# Conn_C.net
KiCad netlist of a schematic drawn in Altium Designer
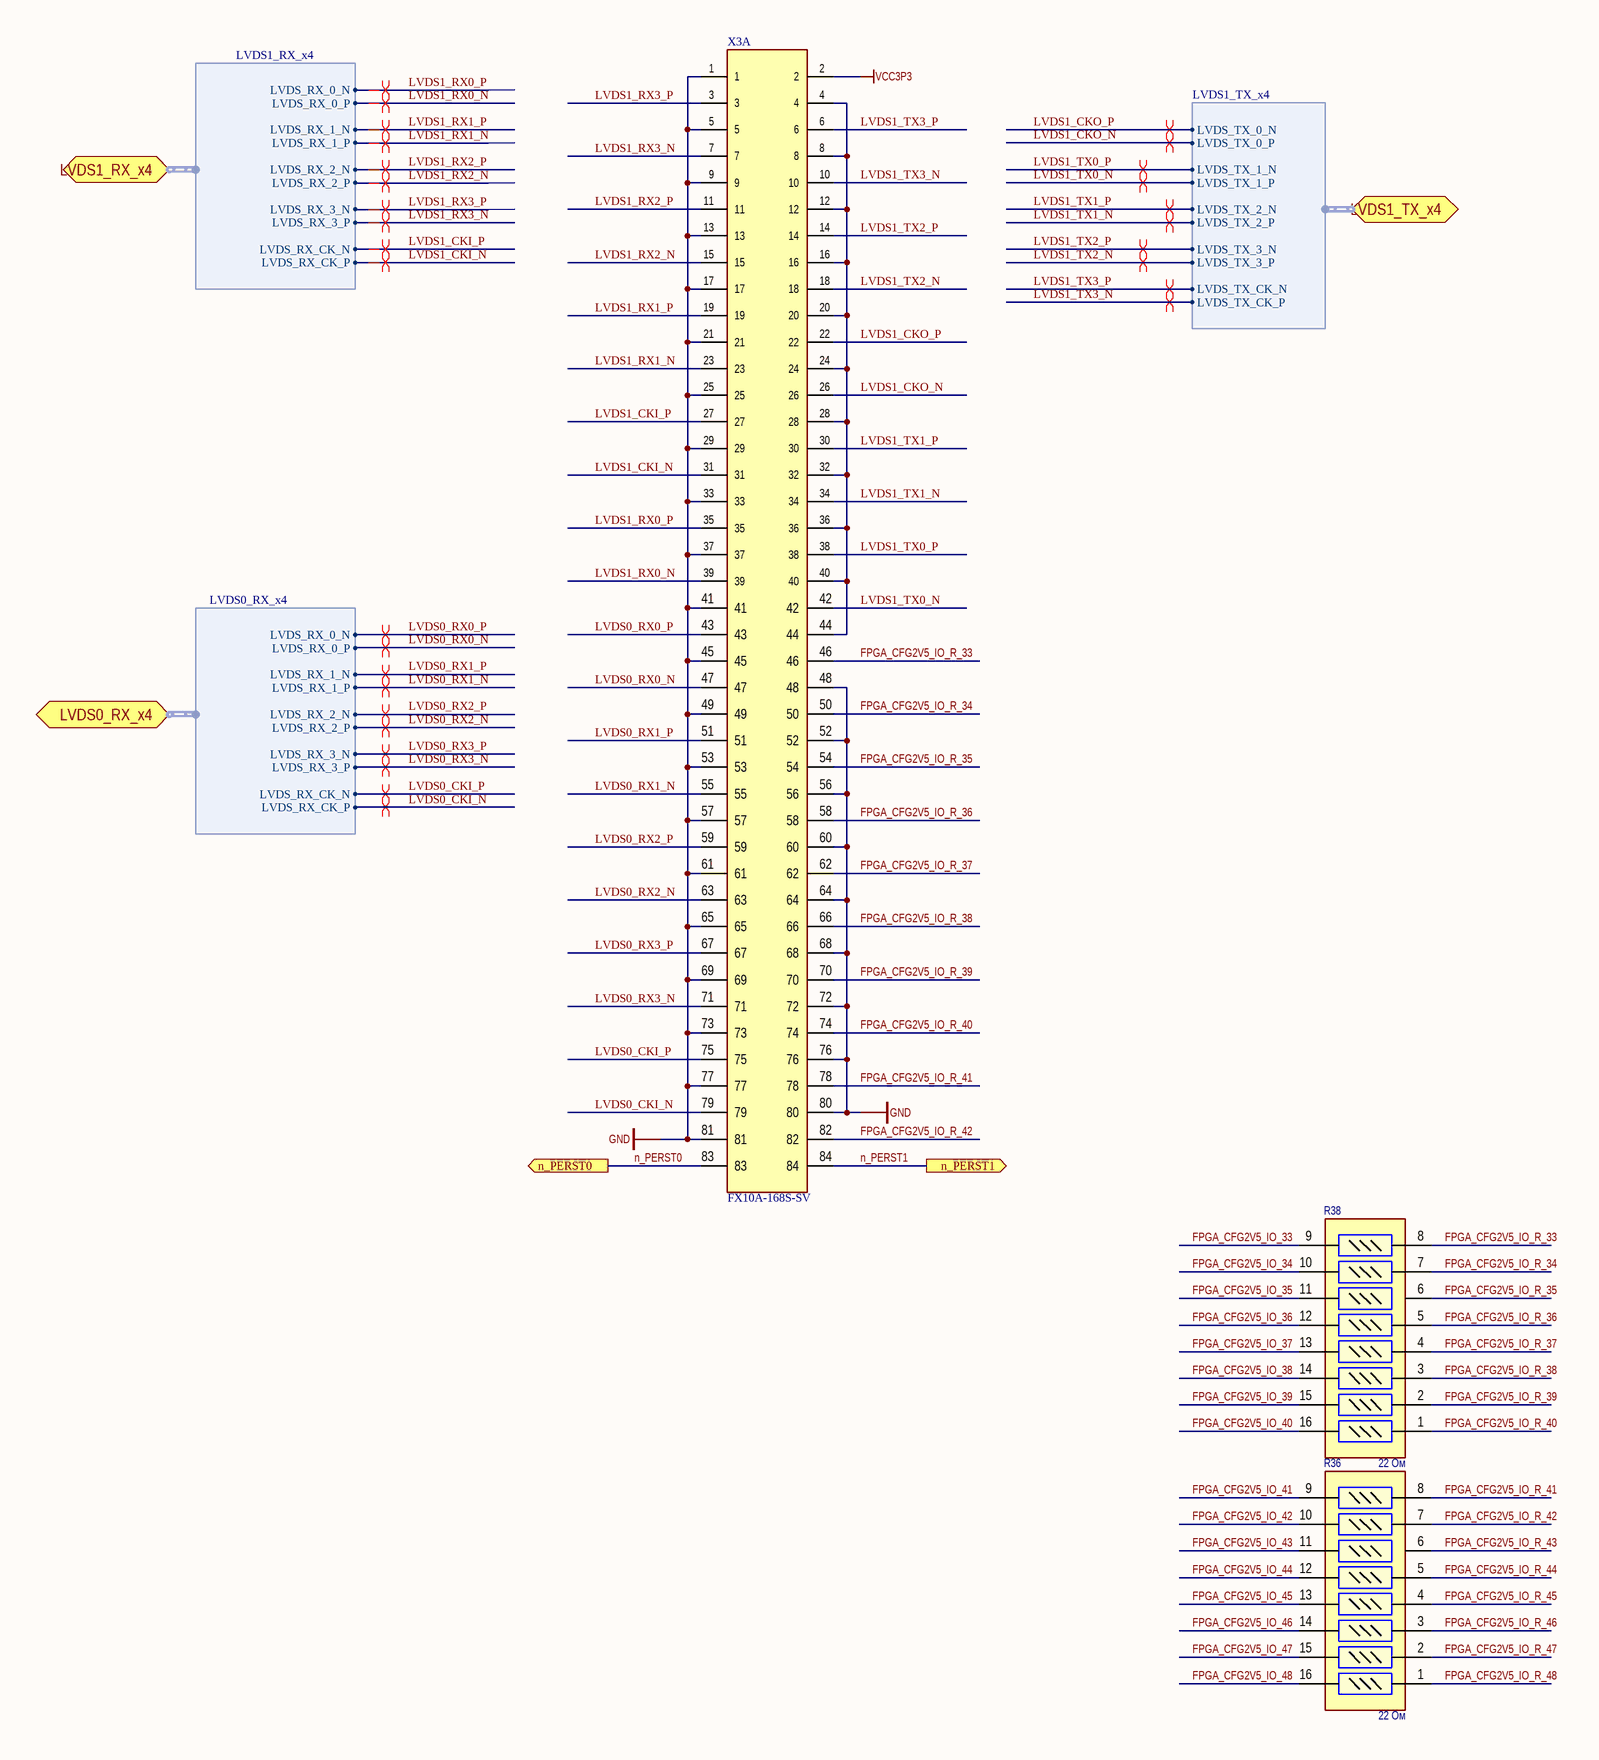
[diagram p0: Conn_C.SchDoc, left]
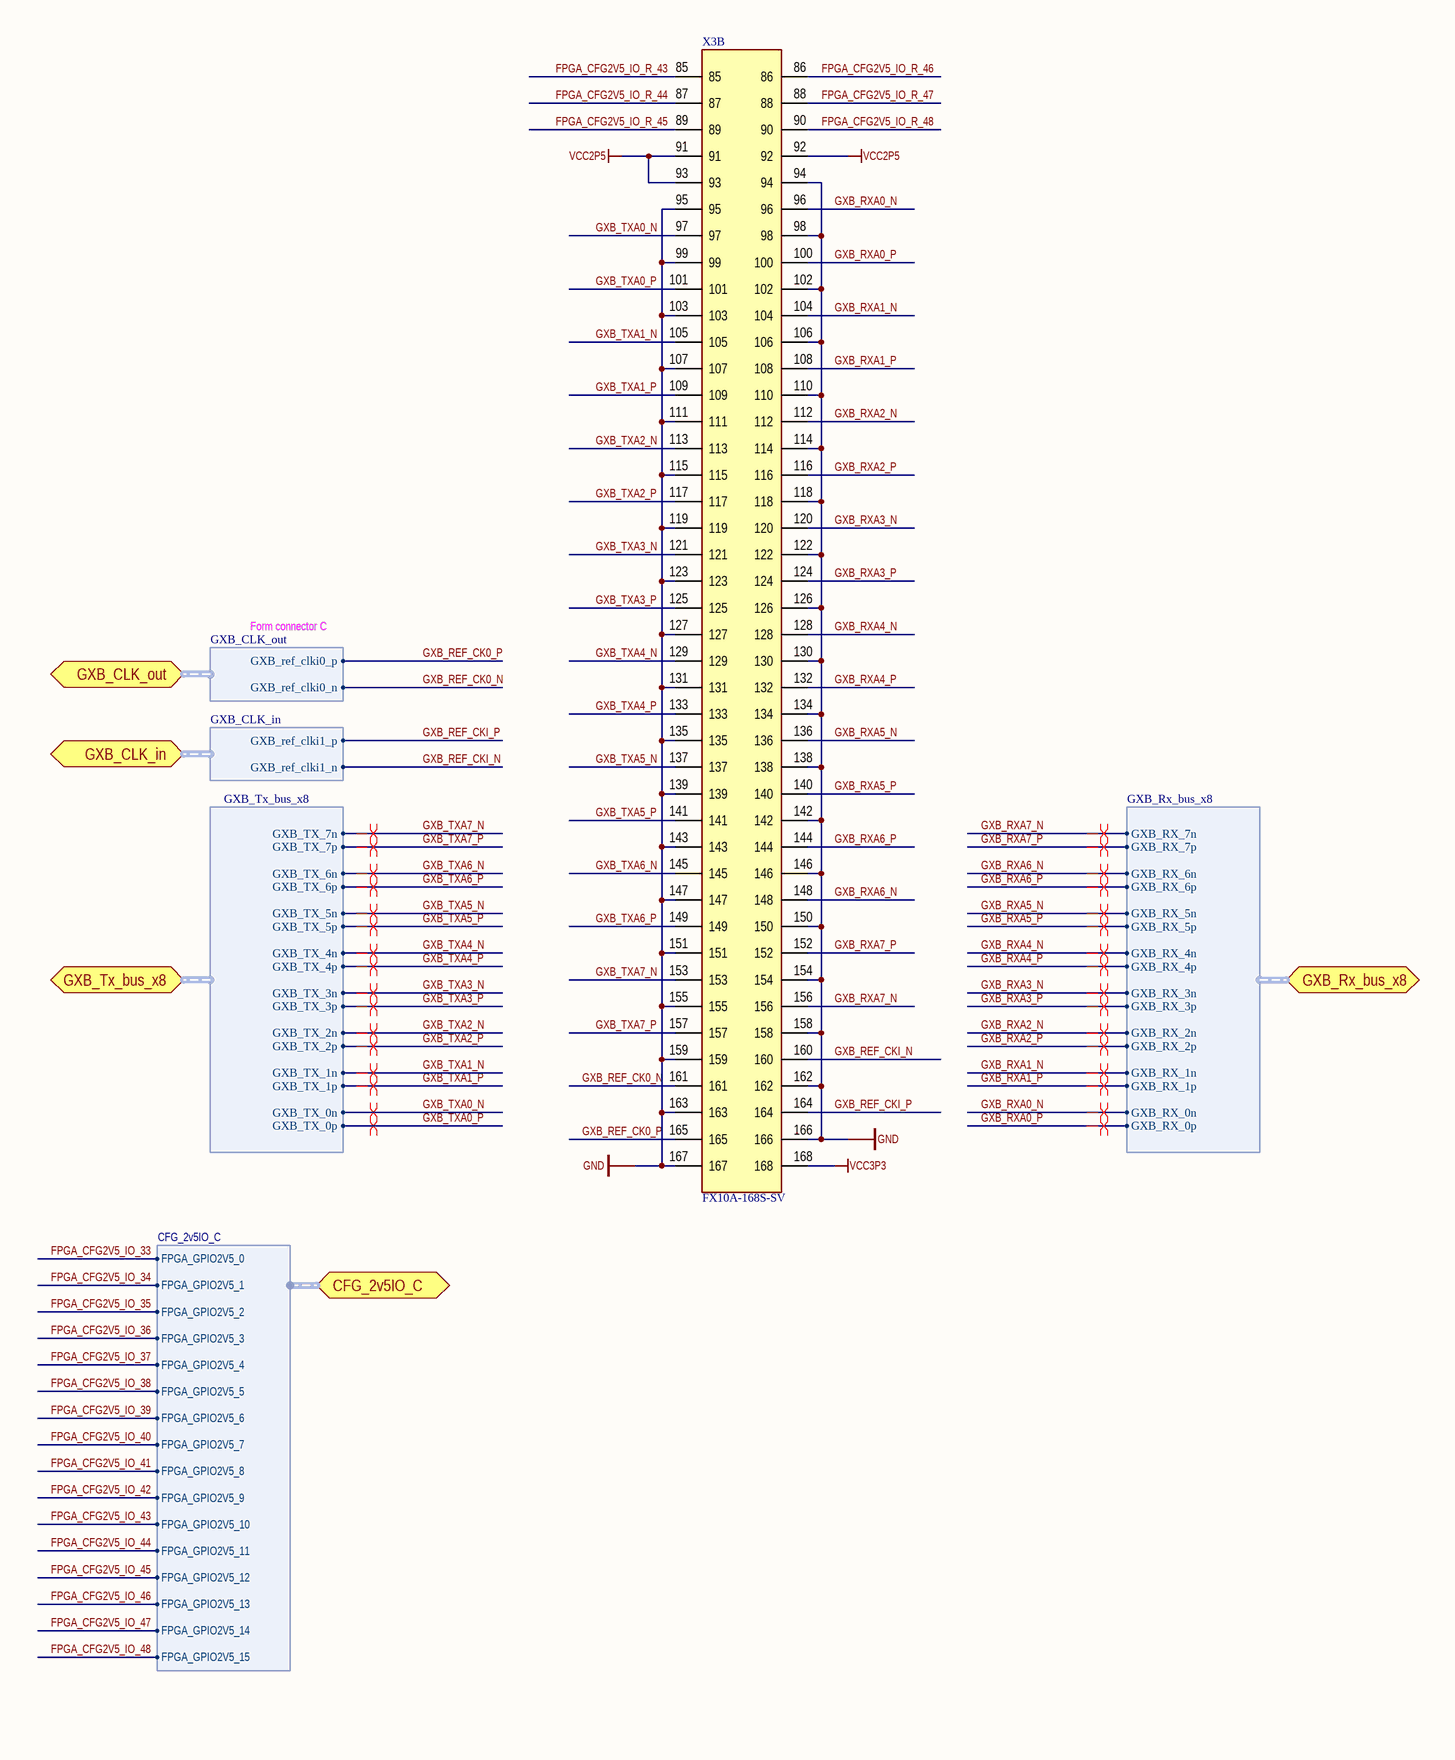
[diagram p1: Conn_C.SchDoc, right]

(export (version "E")
  (design (tool "Eeschema 10.0.6"))
  (components
    (comp (ref "R36")
      (value "22 Ом")
      (footprint "CAT16-J8")
      (description "Набор чип резисторов")
      (fields (field (name "Comment") "YC248-JR-07-22 Ом"))
      (libsource (lib "SD_IC") (part "YC248-JR-07-#"))
    )
    (comp (ref "R38")
      (value "22 Ом")
      (footprint "CAT16-J8")
      (description "Набор чип резисторов")
      (fields (field (name "Comment") "YC248-JR-07-22 Ом"))
      (libsource (lib "SD_IC") (part "YC248-JR-07-#"))
    )
    (comp (ref "X3")
      (value "FX10A-168S-SV")
      (footprint "FX10A-168S-SV")
      (libsource (lib "SD_IC") (part "FX10A-168S-SV"))
    )
  )
  (nets
    (net (code "10") (name "/FPGA_CFG2V5_IO_33") (class "Default")
      (node (ref "R38") (pin "9") (pintype "passive"))
    )
    (net (code "11") (name "/FPGA_CFG2V5_IO_34") (class "Default")
      (node (ref "R38") (pin "10") (pintype "passive"))
    )
    (net (code "12") (name "/FPGA_CFG2V5_IO_35") (class "Default")
      (node (ref "R38") (pin "11") (pintype "passive"))
    )
    (net (code "13") (name "/FPGA_CFG2V5_IO_36") (class "Default")
      (node (ref "R38") (pin "12") (pintype "passive"))
    )
    (net (code "14") (name "/FPGA_CFG2V5_IO_37") (class "Default")
      (node (ref "R38") (pin "13") (pintype "passive"))
    )
    (net (code "15") (name "/FPGA_CFG2V5_IO_38") (class "Default")
      (node (ref "R38") (pin "14") (pintype "passive"))
    )
    (net (code "16") (name "/FPGA_CFG2V5_IO_39") (class "Default")
      (node (ref "R38") (pin "15") (pintype "passive"))
    )
    (net (code "17") (name "/FPGA_CFG2V5_IO_40") (class "Default")
      (node (ref "R38") (pin "16") (pintype "passive"))
    )
    (net (code "18") (name "/FPGA_CFG2V5_IO_41") (class "Default")
      (node (ref "R36") (pin "9") (pintype "passive"))
    )
    (net (code "19") (name "/FPGA_CFG2V5_IO_42") (class "Default")
      (node (ref "R36") (pin "10") (pintype "passive"))
    )
    (net (code "20") (name "/FPGA_CFG2V5_IO_43") (class "Default")
      (node (ref "R36") (pin "11") (pintype "passive"))
    )
    (net (code "21") (name "/FPGA_CFG2V5_IO_44") (class "Default")
      (node (ref "R36") (pin "12") (pintype "passive"))
    )
    (net (code "22") (name "/FPGA_CFG2V5_IO_45") (class "Default")
      (node (ref "R36") (pin "13") (pintype "passive"))
    )
    (net (code "23") (name "/FPGA_CFG2V5_IO_46") (class "Default")
      (node (ref "R36") (pin "14") (pintype "passive"))
    )
    (net (code "24") (name "/FPGA_CFG2V5_IO_47") (class "Default")
      (node (ref "R36") (pin "15") (pintype "passive"))
    )
    (net (code "25") (name "/FPGA_CFG2V5_IO_48") (class "Default")
      (node (ref "R36") (pin "16") (pintype "passive"))
    )
    (net (code "26") (name "/FPGA_CFG2V5_IO_R_33") (class "Default")
      (node (ref "R38") (pin "8") (pintype "passive"))
      (node (ref "X3") (pin "46") (pinfunction "46_46") (pintype "passive"))
    )
    (net (code "27") (name "/FPGA_CFG2V5_IO_R_34") (class "Default")
      (node (ref "R38") (pin "7") (pintype "passive"))
      (node (ref "X3") (pin "50") (pinfunction "50_50") (pintype "passive"))
    )
    (net (code "28") (name "/FPGA_CFG2V5_IO_R_35") (class "Default")
      (node (ref "R38") (pin "6") (pintype "passive"))
      (node (ref "X3") (pin "54") (pinfunction "54_54") (pintype "passive"))
    )
    (net (code "29") (name "/FPGA_CFG2V5_IO_R_36") (class "Default")
      (node (ref "R38") (pin "5") (pintype "passive"))
      (node (ref "X3") (pin "58") (pinfunction "58_58") (pintype "passive"))
    )
    (net (code "30") (name "/FPGA_CFG2V5_IO_R_37") (class "Default")
      (node (ref "R38") (pin "4") (pintype "passive"))
      (node (ref "X3") (pin "62") (pinfunction "62_62") (pintype "passive"))
    )
    (net (code "31") (name "/FPGA_CFG2V5_IO_R_38") (class "Default")
      (node (ref "R38") (pin "3") (pintype "passive"))
      (node (ref "X3") (pin "66") (pinfunction "66_66") (pintype "passive"))
    )
    (net (code "32") (name "/FPGA_CFG2V5_IO_R_39") (class "Default")
      (node (ref "R38") (pin "2") (pintype "passive"))
      (node (ref "X3") (pin "70") (pinfunction "70_70") (pintype "passive"))
    )
    (net (code "33") (name "/FPGA_CFG2V5_IO_R_40") (class "Default")
      (node (ref "R38") (pin "1") (pintype "passive"))
      (node (ref "X3") (pin "74") (pinfunction "74_74") (pintype "passive"))
    )
    (net (code "34") (name "/FPGA_CFG2V5_IO_R_41") (class "Default")
      (node (ref "R36") (pin "8") (pintype "passive"))
      (node (ref "X3") (pin "78") (pinfunction "78_78") (pintype "passive"))
    )
    (net (code "35") (name "/FPGA_CFG2V5_IO_R_42") (class "Default")
      (node (ref "R36") (pin "7") (pintype "passive"))
      (node (ref "X3") (pin "82") (pinfunction "82_82") (pintype "passive"))
    )
    (net (code "36") (name "/FPGA_CFG2V5_IO_R_43") (class "Default")
      (node (ref "R36") (pin "6") (pintype "passive"))
      (node (ref "X3") (pin "85") (pinfunction "85_85") (pintype "passive"))
    )
    (net (code "37") (name "/FPGA_CFG2V5_IO_R_44") (class "Default")
      (node (ref "R36") (pin "5") (pintype "passive"))
      (node (ref "X3") (pin "87") (pinfunction "87_87") (pintype "passive"))
    )
    (net (code "38") (name "/FPGA_CFG2V5_IO_R_45") (class "Default")
      (node (ref "R36") (pin "4") (pintype "passive"))
      (node (ref "X3") (pin "89") (pinfunction "89_89") (pintype "passive"))
    )
    (net (code "39") (name "/FPGA_CFG2V5_IO_R_46") (class "Default")
      (node (ref "R36") (pin "3") (pintype "passive"))
      (node (ref "X3") (pin "86") (pinfunction "86_86") (pintype "passive"))
    )
    (net (code "40") (name "/FPGA_CFG2V5_IO_R_47") (class "Default")
      (node (ref "R36") (pin "2") (pintype "passive"))
      (node (ref "X3") (pin "88") (pinfunction "88_88") (pintype "passive"))
    )
    (net (code "41") (name "/FPGA_CFG2V5_IO_R_48") (class "Default")
      (node (ref "R36") (pin "1") (pintype "passive"))
      (node (ref "X3") (pin "90") (pinfunction "90_90") (pintype "passive"))
    )
    (net (code "42") (name "/GXB_REF_CK0_N") (class "Default")
      (node (ref "X3") (pin "161") (pinfunction "161_161") (pintype "passive"))
    )
    (net (code "43") (name "/GXB_REF_CK0_P") (class "Default")
      (node (ref "X3") (pin "165") (pinfunction "165_165") (pintype "passive"))
    )
    (net (code "44") (name "/GXB_REF_CKI_N") (class "Default")
      (node (ref "X3") (pin "160") (pinfunction "160_160") (pintype "passive"))
    )
    (net (code "45") (name "/GXB_REF_CKI_P") (class "Default")
      (node (ref "X3") (pin "164") (pinfunction "164_164") (pintype "passive"))
    )
    (net (code "46") (name "/GXB_RXA0_N") (class "Default")
      (node (ref "X3") (pin "96") (pinfunction "96_96") (pintype "passive"))
    )
    (net (code "47") (name "/GXB_RXA0_P") (class "Default")
      (node (ref "X3") (pin "100") (pinfunction "100_100") (pintype "passive"))
    )
    (net (code "48") (name "/GXB_RXA1_N") (class "Default")
      (node (ref "X3") (pin "104") (pinfunction "104_104") (pintype "passive"))
    )
    (net (code "49") (name "/GXB_RXA1_P") (class "Default")
      (node (ref "X3") (pin "108") (pinfunction "108_108") (pintype "passive"))
    )
    (net (code "50") (name "/GXB_RXA2_N") (class "Default")
      (node (ref "X3") (pin "112") (pinfunction "112_112") (pintype "passive"))
    )
    (net (code "51") (name "/GXB_RXA2_P") (class "Default")
      (node (ref "X3") (pin "116") (pinfunction "116_116") (pintype "passive"))
    )
    (net (code "52") (name "/GXB_RXA3_N") (class "Default")
      (node (ref "X3") (pin "120") (pinfunction "120_120") (pintype "passive"))
    )
    (net (code "53") (name "/GXB_RXA3_P") (class "Default")
      (node (ref "X3") (pin "124") (pinfunction "124_124") (pintype "passive"))
    )
    (net (code "54") (name "/GXB_RXA4_N") (class "Default")
      (node (ref "X3") (pin "128") (pinfunction "128_128") (pintype "passive"))
    )
    (net (code "55") (name "/GXB_RXA4_P") (class "Default")
      (node (ref "X3") (pin "132") (pinfunction "132_132") (pintype "passive"))
    )
    (net (code "56") (name "/GXB_RXA5_N") (class "Default")
      (node (ref "X3") (pin "136") (pinfunction "136_136") (pintype "passive"))
    )
    (net (code "57") (name "/GXB_RXA5_P") (class "Default")
      (node (ref "X3") (pin "140") (pinfunction "140_140") (pintype "passive"))
    )
    (net (code "58") (name "/GXB_RXA6_N") (class "Default")
      (node (ref "X3") (pin "148") (pinfunction "148_148") (pintype "passive"))
    )
    (net (code "59") (name "/GXB_RXA6_P") (class "Default")
      (node (ref "X3") (pin "144") (pinfunction "144_144") (pintype "passive"))
    )
    (net (code "60") (name "/GXB_RXA7_N") (class "Default")
      (node (ref "X3") (pin "156") (pinfunction "156_156") (pintype "passive"))
    )
    (net (code "61") (name "/GXB_RXA7_P") (class "Default")
      (node (ref "X3") (pin "152") (pinfunction "152_152") (pintype "passive"))
    )
    (net (code "62") (name "/GXB_TXA0_N") (class "Default")
      (node (ref "X3") (pin "97") (pinfunction "97_97") (pintype "passive"))
    )
    (net (code "63") (name "/GXB_TXA0_P") (class "Default")
      (node (ref "X3") (pin "101") (pinfunction "101_101") (pintype "passive"))
    )
    (net (code "64") (name "/GXB_TXA1_N") (class "Default")
      (node (ref "X3") (pin "105") (pinfunction "105_105") (pintype "passive"))
    )
    (net (code "65") (name "/GXB_TXA1_P") (class "Default")
      (node (ref "X3") (pin "109") (pinfunction "109_109") (pintype "passive"))
    )
    (net (code "66") (name "/GXB_TXA2_N") (class "Default")
      (node (ref "X3") (pin "113") (pinfunction "113_113") (pintype "passive"))
    )
    (net (code "67") (name "/GXB_TXA2_P") (class "Default")
      (node (ref "X3") (pin "117") (pinfunction "117_117") (pintype "passive"))
    )
    (net (code "68") (name "/GXB_TXA3_N") (class "Default")
      (node (ref "X3") (pin "121") (pinfunction "121_121") (pintype "passive"))
    )
    (net (code "69") (name "/GXB_TXA3_P") (class "Default")
      (node (ref "X3") (pin "125") (pinfunction "125_125") (pintype "passive"))
    )
    (net (code "70") (name "/GXB_TXA4_N") (class "Default")
      (node (ref "X3") (pin "129") (pinfunction "129_129") (pintype "passive"))
    )
    (net (code "71") (name "/GXB_TXA4_P") (class "Default")
      (node (ref "X3") (pin "133") (pinfunction "133_133") (pintype "passive"))
    )
    (net (code "72") (name "/GXB_TXA5_N") (class "Default")
      (node (ref "X3") (pin "137") (pinfunction "137_137") (pintype "passive"))
    )
    (net (code "73") (name "/GXB_TXA5_P") (class "Default")
      (node (ref "X3") (pin "141") (pinfunction "141_141") (pintype "passive"))
    )
    (net (code "74") (name "/GXB_TXA6_N") (class "Default")
      (node (ref "X3") (pin "145") (pinfunction "145_145") (pintype "passive"))
    )
    (net (code "75") (name "/GXB_TXA6_P") (class "Default")
      (node (ref "X3") (pin "149") (pinfunction "149_149") (pintype "passive"))
    )
    (net (code "76") (name "/GXB_TXA7_N") (class "Default")
      (node (ref "X3") (pin "153") (pinfunction "153_153") (pintype "passive"))
    )
    (net (code "77") (name "/GXB_TXA7_P") (class "Default")
      (node (ref "X3") (pin "157") (pinfunction "157_157") (pintype "passive"))
    )
    (net (code "78") (name "/LVDS0_CKI_N") (class "Default")
      (node (ref "X3") (pin "79") (pinfunction "79_79") (pintype "passive"))
    )
    (net (code "79") (name "/LVDS0_CKI_P") (class "Default")
      (node (ref "X3") (pin "75") (pinfunction "75_75") (pintype "passive"))
    )
    (net (code "80") (name "/LVDS0_RX0_N") (class "Default")
      (node (ref "X3") (pin "47") (pinfunction "47_47") (pintype "passive"))
    )
    (net (code "81") (name "/LVDS0_RX0_P") (class "Default")
      (node (ref "X3") (pin "43") (pinfunction "43_43") (pintype "passive"))
    )
    (net (code "82") (name "/LVDS0_RX1_N") (class "Default")
      (node (ref "X3") (pin "55") (pinfunction "55_55") (pintype "passive"))
    )
    (net (code "83") (name "/LVDS0_RX1_P") (class "Default")
      (node (ref "X3") (pin "51") (pinfunction "51_51") (pintype "passive"))
    )
    (net (code "84") (name "/LVDS0_RX2_N") (class "Default")
      (node (ref "X3") (pin "63") (pinfunction "63_63") (pintype "passive"))
    )
    (net (code "85") (name "/LVDS0_RX2_P") (class "Default")
      (node (ref "X3") (pin "59") (pinfunction "59_59") (pintype "passive"))
    )
    (net (code "86") (name "/LVDS0_RX3_N") (class "Default")
      (node (ref "X3") (pin "71") (pinfunction "71_71") (pintype "passive"))
    )
    (net (code "87") (name "/LVDS0_RX3_P") (class "Default")
      (node (ref "X3") (pin "67") (pinfunction "67_67") (pintype "passive"))
    )
    (net (code "89") (name "/LVDS1_CKI_N") (class "Default")
      (node (ref "X3") (pin "31") (pinfunction "31_31") (pintype "passive"))
    )
    (net (code "90") (name "/LVDS1_CKI_P") (class "Default")
      (node (ref "X3") (pin "27") (pinfunction "27_27") (pintype "passive"))
    )
    (net (code "91") (name "/LVDS1_CKO_N") (class "Default")
      (node (ref "X3") (pin "26") (pinfunction "26_26") (pintype "passive"))
    )
    (net (code "92") (name "/LVDS1_CKO_P") (class "Default")
      (node (ref "X3") (pin "22") (pinfunction "22_22") (pintype "passive"))
    )
    (net (code "93") (name "/LVDS1_RX0_N") (class "Default")
      (node (ref "X3") (pin "39") (pinfunction "39_39") (pintype "passive"))
    )
    (net (code "94") (name "/LVDS1_RX0_P") (class "Default")
      (node (ref "X3") (pin "35") (pinfunction "35_35") (pintype "passive"))
    )
    (net (code "95") (name "/LVDS1_RX1_N") (class "Default")
      (node (ref "X3") (pin "23") (pinfunction "23_23") (pintype "passive"))
    )
    (net (code "96") (name "/LVDS1_RX1_P") (class "Default")
      (node (ref "X3") (pin "19") (pinfunction "19_19") (pintype "passive"))
    )
    (net (code "97") (name "/LVDS1_RX2_N") (class "Default")
      (node (ref "X3") (pin "15") (pinfunction "15_15") (pintype "passive"))
    )
    (net (code "98") (name "/LVDS1_RX2_P") (class "Default")
      (node (ref "X3") (pin "11") (pinfunction "11_11") (pintype "passive"))
    )
    (net (code "99") (name "/LVDS1_RX3_N") (class "Default")
      (node (ref "X3") (pin "7") (pinfunction "7_7") (pintype "passive"))
    )
    (net (code "100") (name "/LVDS1_RX3_P") (class "Default")
      (node (ref "X3") (pin "3") (pinfunction "3_3") (pintype "passive"))
    )
    (net (code "101") (name "/LVDS1_TX0_N") (class "Default")
      (node (ref "X3") (pin "42") (pinfunction "42_42") (pintype "passive"))
    )
    (net (code "102") (name "/LVDS1_TX0_P") (class "Default")
      (node (ref "X3") (pin "38") (pinfunction "38_38") (pintype "passive"))
    )
    (net (code "103") (name "/LVDS1_TX1_N") (class "Default")
      (node (ref "X3") (pin "34") (pinfunction "34_34") (pintype "passive"))
    )
    (net (code "104") (name "/LVDS1_TX1_P") (class "Default")
      (node (ref "X3") (pin "30") (pinfunction "30_30") (pintype "passive"))
    )
    (net (code "105") (name "/LVDS1_TX2_N") (class "Default")
      (node (ref "X3") (pin "18") (pinfunction "18_18") (pintype "passive"))
    )
    (net (code "106") (name "/LVDS1_TX2_P") (class "Default")
      (node (ref "X3") (pin "14") (pinfunction "14_14") (pintype "passive"))
    )
    (net (code "107") (name "/LVDS1_TX3_N") (class "Default")
      (node (ref "X3") (pin "10") (pinfunction "10_10") (pintype "passive"))
    )
    (net (code "108") (name "/LVDS1_TX3_P") (class "Default")
      (node (ref "X3") (pin "6") (pinfunction "6_6") (pintype "passive"))
    )
    (net (code "109") (name "/n_PERST0") (class "Default")
      (node (ref "X3") (pin "83") (pinfunction "83_83") (pintype "passive"))
    )
    (net (code "110") (name "/n_PERST1") (class "Default")
      (node (ref "X3") (pin "84") (pinfunction "84_84") (pintype "passive"))
    )
    (net (code "119") (name "GND") (class "Default")
      (node (ref "X3") (pin "1") (pinfunction "1_1") (pintype "passive"))
      (node (ref "X3") (pin "102") (pinfunction "102_102") (pintype "passive"))
      (node (ref "X3") (pin "103") (pinfunction "103_103") (pintype "passive"))
      (node (ref "X3") (pin "106") (pinfunction "106_106") (pintype "passive"))
      (node (ref "X3") (pin "107") (pinfunction "107_107") (pintype "passive"))
      (node (ref "X3") (pin "110") (pinfunction "110_110") (pintype "passive"))
      (node (ref "X3") (pin "111") (pinfunction "111_111") (pintype "passive"))
      (node (ref "X3") (pin "114") (pinfunction "114_114") (pintype "passive"))
      (node (ref "X3") (pin "115") (pinfunction "115_115") (pintype "passive"))
      (node (ref "X3") (pin "118") (pinfunction "118_118") (pintype "passive"))
      (node (ref "X3") (pin "119") (pinfunction "119_119") (pintype "passive"))
      (node (ref "X3") (pin "122") (pinfunction "122_122") (pintype "passive"))
      (node (ref "X3") (pin "123") (pinfunction "123_123") (pintype "passive"))
      (node (ref "X3") (pin "126") (pinfunction "126_126") (pintype "passive"))
      (node (ref "X3") (pin "127") (pinfunction "127_127") (pintype "passive"))
      (node (ref "X3") (pin "13") (pinfunction "13_13") (pintype "passive"))
      (node (ref "X3") (pin "130") (pinfunction "130_130") (pintype "passive"))
      (node (ref "X3") (pin "131") (pinfunction "131_131") (pintype "passive"))
      (node (ref "X3") (pin "134") (pinfunction "134_134") (pintype "passive"))
      (node (ref "X3") (pin "135") (pinfunction "135_135") (pintype "passive"))
      (node (ref "X3") (pin "138") (pinfunction "138_138") (pintype "passive"))
      (node (ref "X3") (pin "139") (pinfunction "139_139") (pintype "passive"))
      (node (ref "X3") (pin "142") (pinfunction "142_142") (pintype "passive"))
      (node (ref "X3") (pin "143") (pinfunction "143_143") (pintype "passive"))
      (node (ref "X3") (pin "146") (pinfunction "146_146") (pintype "passive"))
      (node (ref "X3") (pin "147") (pinfunction "147_147") (pintype "passive"))
      (node (ref "X3") (pin "150") (pinfunction "150_150") (pintype "passive"))
      (node (ref "X3") (pin "151") (pinfunction "151_151") (pintype "passive"))
      (node (ref "X3") (pin "154") (pinfunction "154_154") (pintype "passive"))
      (node (ref "X3") (pin "155") (pinfunction "155_155") (pintype "passive"))
      (node (ref "X3") (pin "158") (pinfunction "158_158") (pintype "passive"))
      (node (ref "X3") (pin "159") (pinfunction "159_159") (pintype "passive"))
      (node (ref "X3") (pin "162") (pinfunction "162_162") (pintype "passive"))
      (node (ref "X3") (pin "163") (pinfunction "163_163") (pintype "passive"))
      (node (ref "X3") (pin "166") (pinfunction "166_166") (pintype "passive"))
      (node (ref "X3") (pin "167") (pinfunction "167_167") (pintype "passive"))
      (node (ref "X3") (pin "17") (pinfunction "17_17") (pintype "passive"))
      (node (ref "X3") (pin "21") (pinfunction "21_21") (pintype "passive"))
      (node (ref "X3") (pin "25") (pinfunction "25_25") (pintype "passive"))
      (node (ref "X3") (pin "29") (pinfunction "29_29") (pintype "passive"))
      (node (ref "X3") (pin "33") (pinfunction "33_33") (pintype "passive"))
      (node (ref "X3") (pin "37") (pinfunction "37_37") (pintype "passive"))
      (node (ref "X3") (pin "41") (pinfunction "41_41") (pintype "passive"))
      (node (ref "X3") (pin "45") (pinfunction "45_45") (pintype "passive"))
      (node (ref "X3") (pin "48") (pinfunction "48_48") (pintype "passive"))
      (node (ref "X3") (pin "49") (pinfunction "49_49") (pintype "passive"))
      (node (ref "X3") (pin "5") (pinfunction "5_5") (pintype "passive"))
      (node (ref "X3") (pin "52") (pinfunction "52_52") (pintype "passive"))
      (node (ref "X3") (pin "53") (pinfunction "53_53") (pintype "passive"))
      (node (ref "X3") (pin "56") (pinfunction "56_56") (pintype "passive"))
      (node (ref "X3") (pin "57") (pinfunction "57_57") (pintype "passive"))
      (node (ref "X3") (pin "60") (pinfunction "60_60") (pintype "passive"))
      (node (ref "X3") (pin "61") (pinfunction "61_61") (pintype "passive"))
      (node (ref "X3") (pin "64") (pinfunction "64_64") (pintype "passive"))
      (node (ref "X3") (pin "65") (pinfunction "65_65") (pintype "passive"))
      (node (ref "X3") (pin "68") (pinfunction "68_68") (pintype "passive"))
      (node (ref "X3") (pin "69") (pinfunction "69_69") (pintype "passive"))
      (node (ref "X3") (pin "72") (pinfunction "72_72") (pintype "passive"))
      (node (ref "X3") (pin "73") (pinfunction "73_73") (pintype "passive"))
      (node (ref "X3") (pin "76") (pinfunction "76_76") (pintype "passive"))
      (node (ref "X3") (pin "77") (pinfunction "77_77") (pintype "passive"))
      (node (ref "X3") (pin "80") (pinfunction "80_80") (pintype "passive"))
      (node (ref "X3") (pin "81") (pinfunction "81_81") (pintype "passive"))
      (node (ref "X3") (pin "9") (pinfunction "9_9") (pintype "passive"))
      (node (ref "X3") (pin "94") (pinfunction "94_94") (pintype "passive"))
      (node (ref "X3") (pin "95") (pinfunction "95_95") (pintype "passive"))
      (node (ref "X3") (pin "98") (pinfunction "98_98") (pintype "passive"))
      (node (ref "X3") (pin "99") (pinfunction "99_99") (pintype "passive"))
    )
    (net (code "120") (name "Net-(X3-Pad12)") (class "Default")
      (node (ref "X3") (pin "12") (pinfunction "12_12") (pintype "passive"))
      (node (ref "X3") (pin "16") (pinfunction "16_16") (pintype "passive"))
      (node (ref "X3") (pin "20") (pinfunction "20_20") (pintype "passive"))
      (node (ref "X3") (pin "24") (pinfunction "24_24") (pintype "passive"))
      (node (ref "X3") (pin "28") (pinfunction "28_28") (pintype "passive"))
      (node (ref "X3") (pin "32") (pinfunction "32_32") (pintype "passive"))
      (node (ref "X3") (pin "36") (pinfunction "36_36") (pintype "passive"))
      (node (ref "X3") (pin "4") (pinfunction "4_4") (pintype "passive"))
      (node (ref "X3") (pin "40") (pinfunction "40_40") (pintype "passive"))
      (node (ref "X3") (pin "44") (pinfunction "44_44") (pintype "passive"))
      (node (ref "X3") (pin "8") (pinfunction "8_8") (pintype "passive"))
    )
    (net (code "121") (name "VCC2P5") (class "Default")
      (node (ref "X3") (pin "91") (pinfunction "91_91") (pintype "passive"))
      (node (ref "X3") (pin "92") (pinfunction "92_92") (pintype "passive"))
      (node (ref "X3") (pin "93") (pinfunction "93_93") (pintype "passive"))
    )
    (net (code "122") (name "VCC3P3") (class "Default")
      (node (ref "X3") (pin "168") (pinfunction "168_168") (pintype "passive"))
      (node (ref "X3") (pin "2") (pinfunction "2_2") (pintype "passive"))
    )
  )
)
